# main.net
KiCad netlist of a schematic drawn in EAGLE
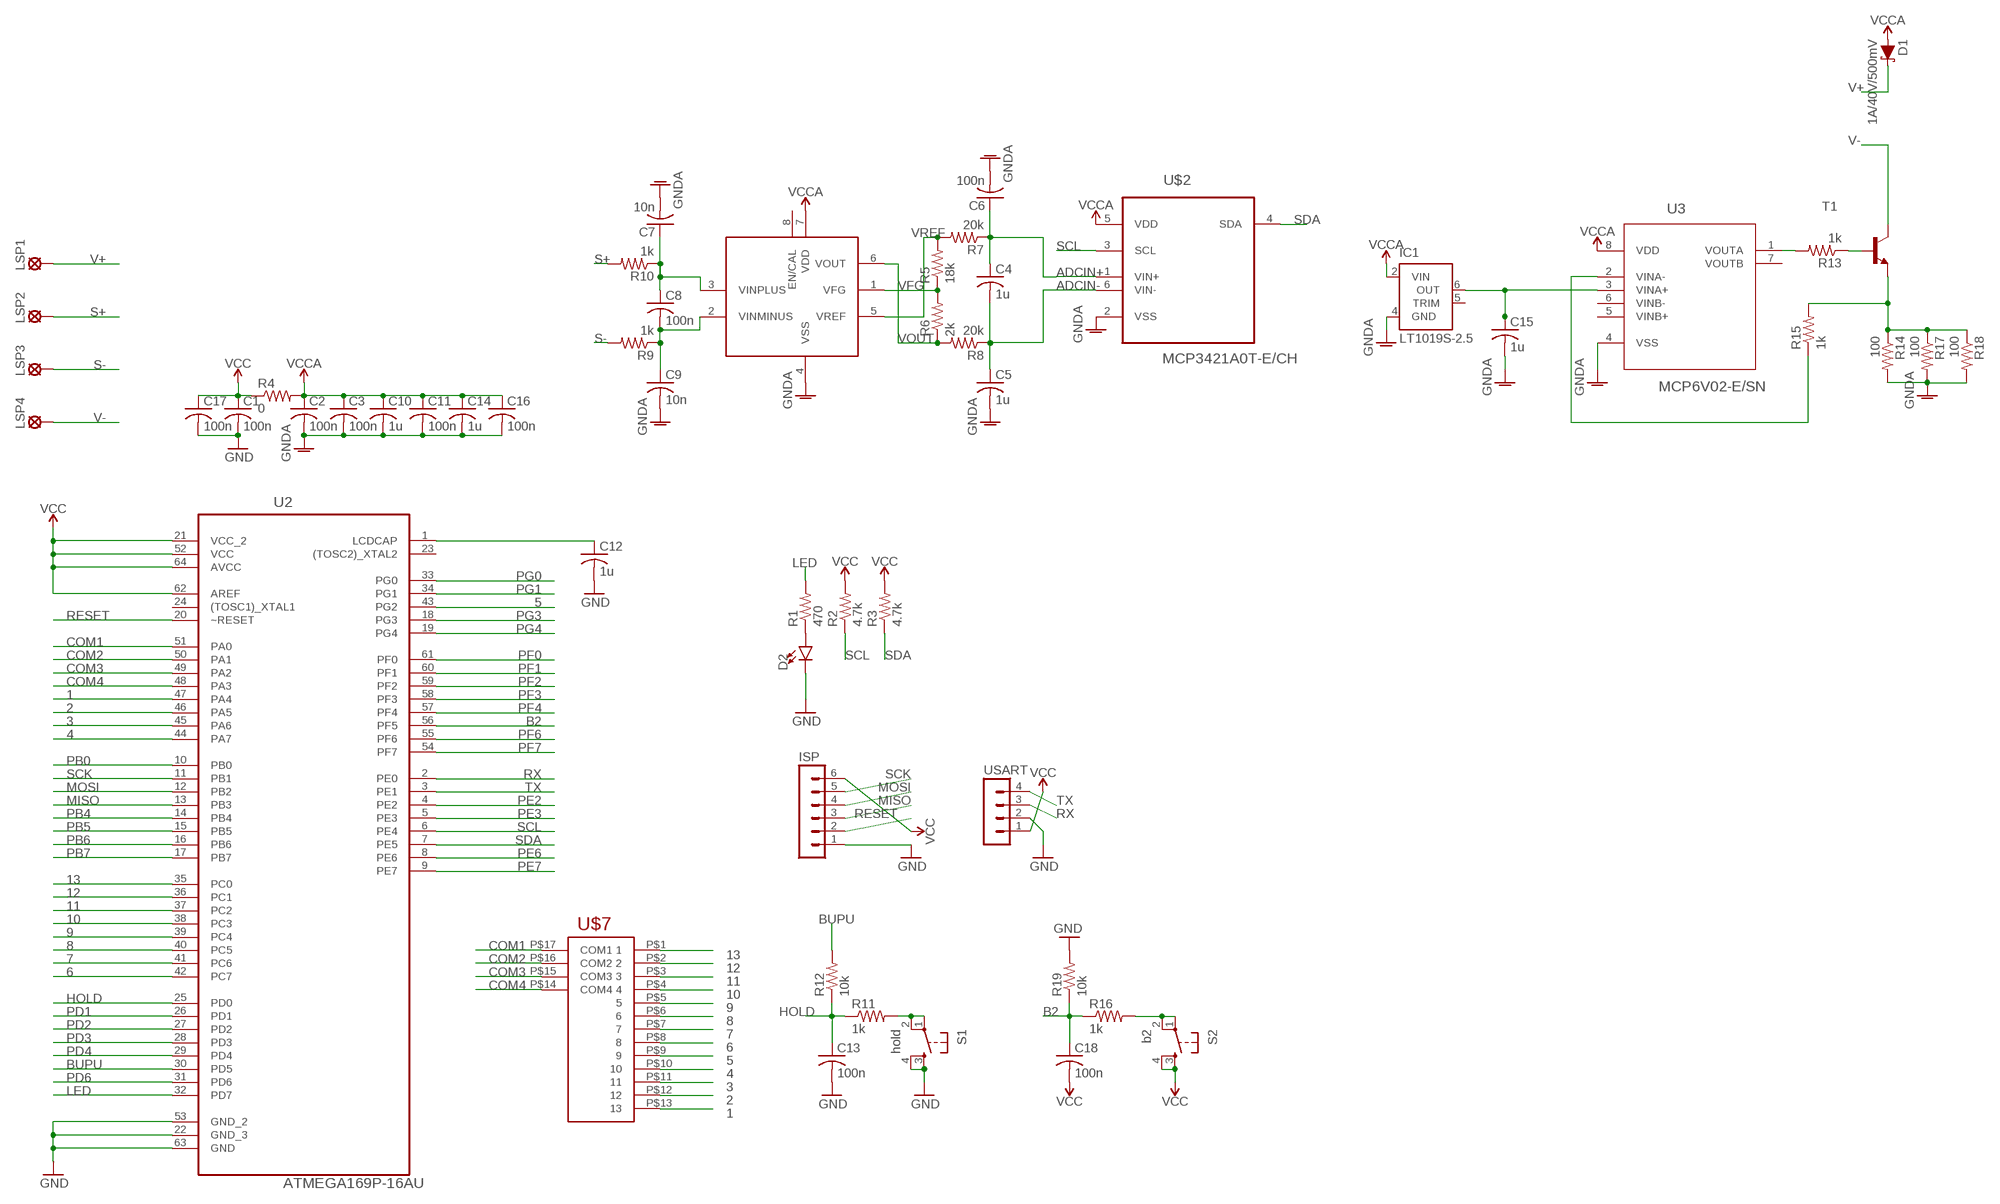
[diagram p0: schematic, sheet 1]

(export (version "E")
  (design (tool "Eeschema 10.0.6"))
  (components
    (comp (ref "C1")
      (value "100n")
      (footprint "eagle-import:C0603")
      (libsource (lib "eagle-import") (part "C-USC0603"))
    )
    (comp (ref "C2")
      (value "100n")
      (footprint "eagle-import:C0603")
      (libsource (lib "eagle-import") (part "C-USC0603"))
    )
    (comp (ref "C3")
      (value "100n")
      (footprint "eagle-import:C0603")
      (libsource (lib "eagle-import") (part "C-USC0603"))
    )
    (comp (ref "C4")
      (value "1u")
      (footprint "eagle-import:C0603")
      (libsource (lib "eagle-import") (part "C-USC0603"))
    )
    (comp (ref "C5")
      (value "1u")
      (footprint "eagle-import:C0603")
      (libsource (lib "eagle-import") (part "C-USC0603"))
    )
    (comp (ref "C6")
      (value "100n")
      (footprint "eagle-import:C0603")
      (libsource (lib "eagle-import") (part "C-USC0603"))
    )
    (comp (ref "C7")
      (value "10n")
      (footprint "eagle-import:C0603")
      (libsource (lib "eagle-import") (part "C-USC0603"))
    )
    (comp (ref "C8")
      (value "100n")
      (footprint "eagle-import:C0603")
      (libsource (lib "eagle-import") (part "C-USC0603"))
    )
    (comp (ref "C9")
      (value "10n")
      (footprint "eagle-import:C0603")
      (libsource (lib "eagle-import") (part "C-USC0603"))
    )
    (comp (ref "C10")
      (value "1u")
      (footprint "eagle-import:C0603")
      (libsource (lib "eagle-import") (part "C-USC0603"))
    )
    (comp (ref "C11")
      (value "100n")
      (footprint "eagle-import:C0603")
      (libsource (lib "eagle-import") (part "C-USC0603"))
    )
    (comp (ref "C12")
      (value "1u")
      (footprint "eagle-import:C0603")
      (libsource (lib "eagle-import") (part "C-USC0603"))
    )
    (comp (ref "C13")
      (value "100n")
      (footprint "eagle-import:C0603")
      (libsource (lib "eagle-import") (part "C-USC0603"))
    )
    (comp (ref "C14")
      (value "1u")
      (footprint "eagle-import:C0603")
      (libsource (lib "eagle-import") (part "C-USC0603"))
    )
    (comp (ref "C15")
      (value "1u")
      (footprint "eagle-import:C0603")
      (libsource (lib "eagle-import") (part "C-USC0603"))
    )
    (comp (ref "C16")
      (value "100n")
      (footprint "eagle-import:C0603")
      (libsource (lib "eagle-import") (part "C-USC0603"))
    )
    (comp (ref "C17")
      (value "100n")
      (footprint "eagle-import:C0603")
      (libsource (lib "eagle-import") (part "C-USC0603"))
    )
    (comp (ref "C18")
      (value "100n")
      (footprint "eagle-import:C0603")
      (libsource (lib "eagle-import") (part "C-USC0603"))
    )
    (comp (ref "D1")
      (value "1A/40V/500mV")
      (footprint "eagle-import:SMA-DIODE")
      (libsource (lib "eagle-import") (part "DIODE-SCHOTTKY-SS14"))
    )
    (comp (ref "D2")
      (value "LED5MM")
      (footprint "eagle-import:LED_5MM")
      (libsource (lib "eagle-import") (part "LED5MM"))
    )
    (comp (ref "IC1")
      (value "LT1019S-2.5")
      (footprint "eagle-import:SOIC8")
      (fields (field (name "MPN") "LT1019CS8-2.5#PBF"))
      (libsource (lib "eagle-import") (part "LT1019?S-2.5"))
    )
    (comp (ref "ISP")
      (value "MA06-1")
      (footprint "eagle-import:MA06-1")
      (libsource (lib "eagle-import") (part "MA06-1"))
    )
    (comp (ref "LSP1")
      (value "MCS08")
      (footprint "eagle-import:MCS08")
      (libsource (lib "eagle-import") (part "MCS08"))
    )
    (comp (ref "LSP2")
      (value "MCS08")
      (footprint "eagle-import:MCS08")
      (libsource (lib "eagle-import") (part "MCS08"))
    )
    (comp (ref "LSP3")
      (value "MCS08")
      (footprint "eagle-import:MCS08")
      (libsource (lib "eagle-import") (part "MCS08"))
    )
    (comp (ref "LSP4")
      (value "MCS08")
      (footprint "eagle-import:MCS08")
      (libsource (lib "eagle-import") (part "MCS08"))
    )
    (comp (ref "R1")
      (value "470")
      (footprint "eagle-import:R0603")
      (libsource (lib "eagle-import") (part "R-US_R0603"))
    )
    (comp (ref "R2")
      (value "4.7k")
      (footprint "eagle-import:R0603")
      (libsource (lib "eagle-import") (part "R-US_R0603"))
    )
    (comp (ref "R3")
      (value "4.7k")
      (footprint "eagle-import:R0603")
      (libsource (lib "eagle-import") (part "R-US_R0603"))
    )
    (comp (ref "R4")
      (value "0")
      (footprint "eagle-import:0309_12")
      (libsource (lib "eagle-import") (part "R-US_0309/12"))
    )
    (comp (ref "R5")
      (value "18k")
      (footprint "eagle-import:R0603")
      (libsource (lib "eagle-import") (part "R-US_R0603"))
    )
    (comp (ref "R6")
      (value "2k")
      (footprint "eagle-import:R0603")
      (libsource (lib "eagle-import") (part "R-US_R0603"))
    )
    (comp (ref "R7")
      (value "20k")
      (footprint "eagle-import:R0603")
      (libsource (lib "eagle-import") (part "R-US_R0603"))
    )
    (comp (ref "R8")
      (value "20k")
      (footprint "eagle-import:R0603")
      (libsource (lib "eagle-import") (part "R-US_R0603"))
    )
    (comp (ref "R9")
      (value "1k")
      (footprint "eagle-import:R0603")
      (libsource (lib "eagle-import") (part "R-US_R0603"))
    )
    (comp (ref "R10")
      (value "1k")
      (footprint "eagle-import:R0603")
      (libsource (lib "eagle-import") (part "R-US_R0603"))
    )
    (comp (ref "R11")
      (value "1k")
      (footprint "eagle-import:R0603")
      (libsource (lib "eagle-import") (part "R-US_R0603"))
    )
    (comp (ref "R12")
      (value "10k")
      (footprint "eagle-import:R0603")
      (libsource (lib "eagle-import") (part "R-US_R0603"))
    )
    (comp (ref "R13")
      (value "1k")
      (footprint "eagle-import:R0603")
      (libsource (lib "eagle-import") (part "R-US_R0603"))
    )
    (comp (ref "R14")
      (value "100")
      (footprint "eagle-import:R0603")
      (libsource (lib "eagle-import") (part "R-US_R0603"))
    )
    (comp (ref "R15")
      (value "1k")
      (footprint "eagle-import:R0603")
      (libsource (lib "eagle-import") (part "R-US_R0603"))
    )
    (comp (ref "R16")
      (value "1k")
      (footprint "eagle-import:R0603")
      (libsource (lib "eagle-import") (part "R-US_R0603"))
    )
    (comp (ref "R17")
      (value "100")
      (footprint "eagle-import:R0603")
      (libsource (lib "eagle-import") (part "R-US_R0603"))
    )
    (comp (ref "R18")
      (value "100")
      (footprint "eagle-import:R0603")
      (libsource (lib "eagle-import") (part "R-US_R0603"))
    )
    (comp (ref "R19")
      (value "10k")
      (footprint "eagle-import:R0603")
      (libsource (lib "eagle-import") (part "R-US_R0603"))
    )
    (comp (ref "S1")
      (value "hold")
      (footprint "eagle-import:TACTILE-PTH")
      (libsource (lib "eagle-import") (part "TAC_SWITCHPTH"))
    )
    (comp (ref "S2")
      (value "b2")
      (footprint "eagle-import:TACTILE-PTH")
      (libsource (lib "eagle-import") (part "TAC_SWITCHPTH"))
    )
    (comp (ref "T1")
      (value "MMBT3904LT1-NPN-SOT23-BEC")
      (footprint "eagle-import:SOT23-BEC")
      (libsource (lib "eagle-import") (part "-NPN-SOT23-BECMMBT3904LT1"))
    )
    (comp (ref "U$2")
      (value "MCP3421A0T-E/CH")
      (footprint "eagle-import:SOT95P270X145-6N")
      (libsource (lib "eagle-import") (part "MCP3421A0T-E/CH"))
    )
    (comp (ref "U$3")
      (value "MCP6N11")
      (footprint "eagle-import:SOIC8")
      (libsource (lib "eagle-import") (part "MCP6N11"))
    )
    (comp (ref "U$7")
      (value "GDC0570_LCD")
      (footprint "eagle-import:GDC0570_LCD")
      (libsource (lib "eagle-import") (part "GDC0570_LCD"))
    )
    (comp (ref "U2")
      (value "ATMEGA169P-16AU")
      (footprint "eagle-import:QFP80P1600X1600X120-64N")
      (libsource (lib "eagle-import") (part "ATMEGA169P-16AU"))
    )
    (comp (ref "U3")
      (value "MCP6V02-E/SN")
      (footprint "eagle-import:SOIC127P600X175-8N")
      (libsource (lib "eagle-import") (part "MCP6V02-E/SN"))
    )
    (comp (ref "USART")
      (value "MA04-1")
      (footprint "eagle-import:MA04-1")
      (libsource (lib "eagle-import") (part "MA04-1"))
    )
  )
  (nets
    (net (code "1") (name "/1") (class "Default")
      (node (ref "U$7") (pin "P$13") (pinfunction "13_P$13") (pintype "bidirectional"))
      (node (ref "U2") (pin "47") (pinfunction "PA4_47") (pintype "bidirectional"))
    )
    (net (code "2") (name "/2") (class "Default")
      (node (ref "U$7") (pin "P$12") (pinfunction "12_P$12") (pintype "bidirectional"))
      (node (ref "U2") (pin "46") (pinfunction "PA5_46") (pintype "bidirectional"))
    )
    (net (code "3") (name "/3") (class "Default")
      (node (ref "U$7") (pin "P$11") (pinfunction "11_P$11") (pintype "bidirectional"))
      (node (ref "U2") (pin "45") (pinfunction "PA6_45") (pintype "bidirectional"))
    )
    (net (code "4") (name "/4") (class "Default")
      (node (ref "U$7") (pin "P$10") (pinfunction "10_P$10") (pintype "bidirectional"))
      (node (ref "U2") (pin "44") (pinfunction "PA7_44") (pintype "bidirectional"))
    )
    (net (code "5") (name "/5") (class "Default")
      (node (ref "U$7") (pin "P$9") (pinfunction "9_P$9") (pintype "bidirectional"))
      (node (ref "U2") (pin "43") (pinfunction "PG2_43") (pintype "bidirectional"))
    )
    (net (code "6") (name "/6") (class "Default")
      (node (ref "U$7") (pin "P$8") (pinfunction "8_P$8") (pintype "bidirectional"))
      (node (ref "U2") (pin "42") (pinfunction "PC7_42") (pintype "bidirectional"))
    )
    (net (code "7") (name "/7") (class "Default")
      (node (ref "U$7") (pin "P$7") (pinfunction "7_P$7") (pintype "bidirectional"))
      (node (ref "U2") (pin "41") (pinfunction "PC6_41") (pintype "bidirectional"))
    )
    (net (code "8") (name "/8") (class "Default")
      (node (ref "U$7") (pin "P$6") (pinfunction "6_P$6") (pintype "bidirectional"))
      (node (ref "U2") (pin "40") (pinfunction "PC5_40") (pintype "bidirectional"))
    )
    (net (code "9") (name "/9") (class "Default")
      (node (ref "U$7") (pin "P$5") (pinfunction "5_P$5") (pintype "bidirectional"))
      (node (ref "U2") (pin "39") (pinfunction "PC4_39") (pintype "bidirectional"))
    )
    (net (code "10") (name "/10") (class "Default")
      (node (ref "U$7") (pin "P$4") (pinfunction "4_P$4") (pintype "bidirectional"))
      (node (ref "U2") (pin "38") (pinfunction "PC3_38") (pintype "bidirectional"))
    )
    (net (code "11") (name "/11") (class "Default")
      (node (ref "U$7") (pin "P$3") (pinfunction "3_P$3") (pintype "bidirectional"))
      (node (ref "U2") (pin "37") (pinfunction "PC2_37") (pintype "bidirectional"))
    )
    (net (code "12") (name "/12") (class "Default")
      (node (ref "U$7") (pin "P$2") (pinfunction "2_P$2") (pintype "bidirectional"))
      (node (ref "U2") (pin "36") (pinfunction "PC1_36") (pintype "bidirectional"))
    )
    (net (code "13") (name "/13") (class "Default")
      (node (ref "U$7") (pin "P$1") (pinfunction "1_P$1") (pintype "bidirectional"))
      (node (ref "U2") (pin "35") (pinfunction "PC0_35") (pintype "bidirectional"))
    )
    (net (code "14") (name "/ADCIN+") (class "Default")
      (node (ref "C4") (pin "1") (pinfunction "1_1") (pintype "passive"))
      (node (ref "C6") (pin "1") (pinfunction "1_1") (pintype "passive"))
      (node (ref "R7") (pin "1") (pinfunction "1_1") (pintype "passive"))
      (node (ref "U$2") (pin "1") (pinfunction "VIN+_1") (pintype "input"))
    )
    (net (code "15") (name "/ADCIN-") (class "Default")
      (node (ref "C4") (pin "2") (pinfunction "2_2") (pintype "passive"))
      (node (ref "C5") (pin "1") (pinfunction "1_1") (pintype "passive"))
      (node (ref "R8") (pin "1") (pinfunction "1_1") (pintype "passive"))
      (node (ref "U$2") (pin "6") (pinfunction "VIN-_6") (pintype "input"))
    )
    (net (code "16") (name "/B2") (class "Default")
      (node (ref "C18") (pin "1") (pinfunction "1_1") (pintype "passive"))
      (node (ref "R16") (pin "1") (pinfunction "1_1") (pintype "passive"))
      (node (ref "R19") (pin "1") (pinfunction "1_1") (pintype "passive"))
      (node (ref "U2") (pin "56") (pinfunction "PF5_56") (pintype "bidirectional"))
    )
    (net (code "17") (name "/BUPU") (class "Default")
      (node (ref "R12") (pin "2") (pinfunction "2_2") (pintype "passive"))
      (node (ref "U2") (pin "30") (pinfunction "PD5_30") (pintype "bidirectional"))
    )
    (net (code "18") (name "/COM1") (class "Default")
      (node (ref "U$7") (pin "P$17") (pinfunction "COM1_P$17") (pintype "bidirectional"))
      (node (ref "U2") (pin "51") (pinfunction "PA0_51") (pintype "bidirectional"))
    )
    (net (code "19") (name "/COM2") (class "Default")
      (node (ref "U$7") (pin "P$16") (pinfunction "COM2_P$16") (pintype "bidirectional"))
      (node (ref "U2") (pin "50") (pinfunction "PA1_50") (pintype "bidirectional"))
    )
    (net (code "20") (name "/COM3") (class "Default")
      (node (ref "U$7") (pin "P$15") (pinfunction "COM3_P$15") (pintype "bidirectional"))
      (node (ref "U2") (pin "49") (pinfunction "PA2_49") (pintype "bidirectional"))
    )
    (net (code "21") (name "/COM4") (class "Default")
      (node (ref "U$7") (pin "P$14") (pinfunction "COM4_P$14") (pintype "bidirectional"))
      (node (ref "U2") (pin "48") (pinfunction "PA3_48") (pintype "bidirectional"))
    )
    (net (code "22") (name "/HOLD") (class "Default")
      (node (ref "C13") (pin "1") (pinfunction "1_1") (pintype "passive"))
      (node (ref "R11") (pin "1") (pinfunction "1_1") (pintype "passive"))
      (node (ref "R12") (pin "1") (pinfunction "1_1") (pintype "passive"))
      (node (ref "U2") (pin "25") (pinfunction "PD0_25") (pintype "bidirectional"))
    )
    (net (code "23") (name "/LED") (class "Default")
      (node (ref "R1") (pin "2") (pinfunction "2_2") (pintype "passive"))
      (node (ref "U2") (pin "32") (pinfunction "PD7_32") (pintype "bidirectional"))
    )
    (net (code "24") (name "/MISO") (class "Default")
      (node (ref "ISP") (pin "3") (pinfunction "3_3") (pintype "passive"))
      (node (ref "U2") (pin "13") (pinfunction "PB3_13") (pintype "bidirectional"))
    )
    (net (code "25") (name "/MOSI") (class "Default")
      (node (ref "ISP") (pin "4") (pinfunction "4_4") (pintype "passive"))
      (node (ref "U2") (pin "12") (pinfunction "PB2_12") (pintype "bidirectional"))
    )
    (net (code "26") (name "/PB0") (class "Default")
      (node (ref "U2") (pin "10") (pinfunction "PB0_10") (pintype "bidirectional"))
    )
    (net (code "27") (name "/PB4") (class "Default")
      (node (ref "U2") (pin "14") (pinfunction "PB4_14") (pintype "bidirectional"))
    )
    (net (code "28") (name "/PB5") (class "Default")
      (node (ref "U2") (pin "15") (pinfunction "PB5_15") (pintype "bidirectional"))
    )
    (net (code "29") (name "/PB6") (class "Default")
      (node (ref "U2") (pin "16") (pinfunction "PB6_16") (pintype "bidirectional"))
    )
    (net (code "30") (name "/PB7") (class "Default")
      (node (ref "U2") (pin "17") (pinfunction "PB7_17") (pintype "bidirectional"))
    )
    (net (code "31") (name "/PD1") (class "Default")
      (node (ref "U2") (pin "26") (pinfunction "PD1_26") (pintype "bidirectional"))
    )
    (net (code "32") (name "/PD2") (class "Default")
      (node (ref "U2") (pin "27") (pinfunction "PD2_27") (pintype "bidirectional"))
    )
    (net (code "33") (name "/PD3") (class "Default")
      (node (ref "U2") (pin "28") (pinfunction "PD3_28") (pintype "bidirectional"))
    )
    (net (code "34") (name "/PD4") (class "Default")
      (node (ref "U2") (pin "29") (pinfunction "PD4_29") (pintype "bidirectional"))
    )
    (net (code "35") (name "/PD6") (class "Default")
      (node (ref "U2") (pin "31") (pinfunction "PD6_31") (pintype "bidirectional"))
    )
    (net (code "36") (name "/PE2") (class "Default")
      (node (ref "U2") (pin "4") (pinfunction "PE2_4") (pintype "bidirectional"))
    )
    (net (code "37") (name "/PE3") (class "Default")
      (node (ref "U2") (pin "5") (pinfunction "PE3_5") (pintype "bidirectional"))
    )
    (net (code "38") (name "/PE6") (class "Default")
      (node (ref "U2") (pin "8") (pinfunction "PE6_8") (pintype "bidirectional"))
    )
    (net (code "39") (name "/PE7") (class "Default")
      (node (ref "U2") (pin "9") (pinfunction "PE7_9") (pintype "bidirectional"))
    )
    (net (code "40") (name "/PF0") (class "Default")
      (node (ref "U2") (pin "61") (pinfunction "PF0_61") (pintype "bidirectional"))
    )
    (net (code "41") (name "/PF1") (class "Default")
      (node (ref "U2") (pin "60") (pinfunction "PF1_60") (pintype "bidirectional"))
    )
    (net (code "42") (name "/PF2") (class "Default")
      (node (ref "U2") (pin "59") (pinfunction "PF2_59") (pintype "bidirectional"))
    )
    (net (code "43") (name "/PF3") (class "Default")
      (node (ref "U2") (pin "58") (pinfunction "PF3_58") (pintype "bidirectional"))
    )
    (net (code "44") (name "/PF4") (class "Default")
      (node (ref "U2") (pin "57") (pinfunction "PF4_57") (pintype "bidirectional"))
    )
    (net (code "45") (name "/PF6") (class "Default")
      (node (ref "U2") (pin "55") (pinfunction "PF6_55") (pintype "bidirectional"))
    )
    (net (code "46") (name "/PF7") (class "Default")
      (node (ref "U2") (pin "54") (pinfunction "PF7_54") (pintype "bidirectional"))
    )
    (net (code "47") (name "/PG0") (class "Default")
      (node (ref "U2") (pin "33") (pinfunction "PG0_33") (pintype "bidirectional"))
    )
    (net (code "48") (name "/PG1") (class "Default")
      (node (ref "U2") (pin "34") (pinfunction "PG1_34") (pintype "bidirectional"))
    )
    (net (code "49") (name "/PG3") (class "Default")
      (node (ref "U2") (pin "18") (pinfunction "PG3_18") (pintype "bidirectional"))
    )
    (net (code "50") (name "/PG4") (class "Default")
      (node (ref "U2") (pin "19") (pinfunction "PG4_19") (pintype "bidirectional"))
    )
    (net (code "51") (name "/RESET") (class "Default")
      (node (ref "ISP") (pin "2") (pinfunction "2_2") (pintype "passive"))
      (node (ref "U2") (pin "20") (pinfunction "~{RESET}_20") (pintype "input"))
    )
    (net (code "52") (name "/RX") (class "Default")
      (node (ref "U2") (pin "2") (pinfunction "PE0_2") (pintype "bidirectional"))
      (node (ref "USART") (pin "3") (pinfunction "3_3") (pintype "passive"))
    )
    (net (code "53") (name "/S+") (class "Default")
      (node (ref "LSP2") (pin "MP") (pinfunction "MP_MP") (pintype "passive"))
      (node (ref "R10") (pin "2") (pinfunction "2_2") (pintype "passive"))
    )
    (net (code "54") (name "/S-") (class "Default")
      (node (ref "LSP3") (pin "MP") (pinfunction "MP_MP") (pintype "passive"))
      (node (ref "R9") (pin "2") (pinfunction "2_2") (pintype "passive"))
    )
    (net (code "55") (name "/SCK") (class "Default")
      (node (ref "ISP") (pin "5") (pinfunction "5_5") (pintype "passive"))
      (node (ref "U2") (pin "11") (pinfunction "PB1_11") (pintype "bidirectional"))
    )
    (net (code "56") (name "/SCL") (class "Default")
      (node (ref "R2") (pin "1") (pinfunction "1_1") (pintype "passive"))
      (node (ref "U$2") (pin "3") (pinfunction "SCL_3") (pintype "input"))
      (node (ref "U2") (pin "6") (pinfunction "PE4_6") (pintype "bidirectional"))
    )
    (net (code "57") (name "/SDA") (class "Default")
      (node (ref "R3") (pin "1") (pinfunction "1_1") (pintype "passive"))
      (node (ref "U$2") (pin "4") (pinfunction "SDA_4") (pintype "bidirectional"))
      (node (ref "U2") (pin "7") (pinfunction "PE5_7") (pintype "bidirectional"))
    )
    (net (code "58") (name "/TX") (class "Default")
      (node (ref "U2") (pin "3") (pinfunction "PE1_3") (pintype "bidirectional"))
      (node (ref "USART") (pin "4") (pinfunction "4_4") (pintype "passive"))
    )
    (net (code "59") (name "/V+") (class "Default")
      (node (ref "D1") (pin "C") (pinfunction "C_C") (pintype "passive"))
      (node (ref "LSP1") (pin "MP") (pinfunction "MP_MP") (pintype "passive"))
    )
    (net (code "60") (name "/V-") (class "Default")
      (node (ref "LSP4") (pin "MP") (pinfunction "MP_MP") (pintype "passive"))
      (node (ref "T1") (pin "C") (pinfunction "C_C") (pintype "passive"))
    )
    (net (code "61") (name "/VFG") (class "Default")
      (node (ref "R5") (pin "1") (pinfunction "1_1") (pintype "passive"))
      (node (ref "R6") (pin "2") (pinfunction "2_2") (pintype "passive"))
      (node (ref "U$3") (pin "1") (pinfunction "VFG_1") (pintype "bidirectional"))
    )
    (net (code "62") (name "/VOUT") (class "Default")
      (node (ref "R6") (pin "1") (pinfunction "1_1") (pintype "passive"))
      (node (ref "R8") (pin "2") (pinfunction "2_2") (pintype "passive"))
      (node (ref "U$3") (pin "6") (pinfunction "VOUT_6") (pintype "bidirectional"))
    )
    (net (code "63") (name "/VREF") (class "Default")
      (node (ref "R5") (pin "2") (pinfunction "2_2") (pintype "passive"))
      (node (ref "R7") (pin "2") (pinfunction "2_2") (pintype "passive"))
      (node (ref "U$3") (pin "5") (pinfunction "VREF_5") (pintype "bidirectional"))
    )
    (net (code "64") (name "GND") (class "Default")
      (node (ref "C1") (pin "2") (pinfunction "2_2") (pintype "passive"))
      (node (ref "C12") (pin "2") (pinfunction "2_2") (pintype "passive"))
      (node (ref "C13") (pin "2") (pinfunction "2_2") (pintype "passive"))
      (node (ref "C17") (pin "2") (pinfunction "2_2") (pintype "passive"))
      (node (ref "D2") (pin "K") (pinfunction "C_K") (pintype "passive"))
      (node (ref "ISP") (pin "1") (pinfunction "1_1") (pintype "passive"))
      (node (ref "R19") (pin "2") (pinfunction "2_2") (pintype "passive"))
      (node (ref "S1") (pin "3") (pinfunction "3_3") (pintype "passive"))
      (node (ref "S1") (pin "4") (pinfunction "4_4") (pintype "passive"))
      (node (ref "U2") (pin "22") (pinfunction "GND_3_22") (pintype "passive"))
      (node (ref "U2") (pin "53") (pinfunction "GND_2_53") (pintype "passive"))
      (node (ref "U2") (pin "63") (pinfunction "GND_63") (pintype "passive"))
      (node (ref "USART") (pin "2") (pinfunction "2_2") (pintype "passive"))
    )
    (net (code "65") (name "GNDA") (class "Default")
      (node (ref "C10") (pin "2") (pinfunction "2_2") (pintype "passive"))
      (node (ref "C11") (pin "2") (pinfunction "2_2") (pintype "passive"))
      (node (ref "C14") (pin "2") (pinfunction "2_2") (pintype "passive"))
      (node (ref "C15") (pin "2") (pinfunction "2_2") (pintype "passive"))
      (node (ref "C16") (pin "2") (pinfunction "2_2") (pintype "passive"))
      (node (ref "C2") (pin "2") (pinfunction "2_2") (pintype "passive"))
      (node (ref "C3") (pin "2") (pinfunction "2_2") (pintype "passive"))
      (node (ref "C5") (pin "2") (pinfunction "2_2") (pintype "passive"))
      (node (ref "C6") (pin "2") (pinfunction "2_2") (pintype "passive"))
      (node (ref "C7") (pin "2") (pinfunction "2_2") (pintype "passive"))
      (node (ref "C9") (pin "2") (pinfunction "2_2") (pintype "passive"))
      (node (ref "IC1") (pin "4") (pinfunction "GND_4") (pintype "power_in"))
      (node (ref "R14") (pin "2") (pinfunction "2_2") (pintype "passive"))
      (node (ref "R17") (pin "2") (pinfunction "2_2") (pintype "passive"))
      (node (ref "R18") (pin "2") (pinfunction "2_2") (pintype "passive"))
      (node (ref "U$2") (pin "2") (pinfunction "VSS_2") (pintype "passive"))
      (node (ref "U$3") (pin "4") (pinfunction "VSS_4") (pintype "bidirectional"))
      (node (ref "U3") (pin "4") (pinfunction "VSS_4") (pintype "power_in"))
    )
    (net (code "66") (name "Net-(D2-PadA)") (class "Default")
      (node (ref "D2") (pin "A") (pinfunction "A_A") (pintype "passive"))
      (node (ref "R1") (pin "1") (pinfunction "1_1") (pintype "passive"))
    )
    (net (code "67") (name "Net-(IC1-OUT)") (class "Default")
      (node (ref "C15") (pin "1") (pinfunction "1_1") (pintype "passive"))
      (node (ref "IC1") (pin "6") (pinfunction "OUT_6") (pintype "input"))
      (node (ref "U3") (pin "3") (pinfunction "VINA+_3") (pintype "input"))
    )
    (net (code "68") (name "Net-(R11-Pad2)") (class "Default")
      (node (ref "R11") (pin "2") (pinfunction "2_2") (pintype "passive"))
      (node (ref "S1") (pin "1") (pinfunction "1_1") (pintype "passive"))
      (node (ref "S1") (pin "2") (pinfunction "2_2") (pintype "passive"))
    )
    (net (code "69") (name "Net-(R13-Pad1)") (class "Default")
      (node (ref "R13") (pin "1") (pinfunction "1_1") (pintype "passive"))
      (node (ref "T1") (pin "B") (pinfunction "B_B") (pintype "passive"))
    )
    (net (code "70") (name "Net-(R14-Pad1)") (class "Default")
      (node (ref "R14") (pin "1") (pinfunction "1_1") (pintype "passive"))
      (node (ref "R15") (pin "2") (pinfunction "2_2") (pintype "passive"))
      (node (ref "R17") (pin "1") (pinfunction "1_1") (pintype "passive"))
      (node (ref "R18") (pin "1") (pinfunction "1_1") (pintype "passive"))
      (node (ref "T1") (pin "E") (pinfunction "E_E") (pintype "passive"))
    )
    (net (code "71") (name "Net-(R16-Pad2)") (class "Default")
      (node (ref "R16") (pin "2") (pinfunction "2_2") (pintype "passive"))
      (node (ref "S2") (pin "1") (pinfunction "1_1") (pintype "passive"))
      (node (ref "S2") (pin "2") (pinfunction "2_2") (pintype "passive"))
    )
    (net (code "72") (name "Net-(U$3-VINMINUS)") (class "Default")
      (node (ref "C8") (pin "2") (pinfunction "2_2") (pintype "passive"))
      (node (ref "C9") (pin "1") (pinfunction "1_1") (pintype "passive"))
      (node (ref "R9") (pin "1") (pinfunction "1_1") (pintype "passive"))
      (node (ref "U$3") (pin "2") (pinfunction "VINMINUS_2") (pintype "bidirectional"))
    )
    (net (code "73") (name "Net-(U$3-VINPLUS)") (class "Default")
      (node (ref "C7") (pin "1") (pinfunction "1_1") (pintype "passive"))
      (node (ref "C8") (pin "1") (pinfunction "1_1") (pintype "passive"))
      (node (ref "R10") (pin "1") (pinfunction "1_1") (pintype "passive"))
      (node (ref "U$3") (pin "3") (pinfunction "VINPLUS_3") (pintype "bidirectional"))
    )
    (net (code "74") (name "Net-(U2-LCDCAP)") (class "Default")
      (node (ref "C12") (pin "1") (pinfunction "1_1") (pintype "passive"))
      (node (ref "U2") (pin "1") (pinfunction "LCDCAP_1") (pintype "passive"))
    )
    (net (code "75") (name "Net-(U3-VINA-)") (class "Default")
      (node (ref "R15") (pin "1") (pinfunction "1_1") (pintype "passive"))
      (node (ref "U3") (pin "2") (pinfunction "VINA-_2") (pintype "input"))
    )
    (net (code "76") (name "Net-(U3-VOUTA)") (class "Default")
      (node (ref "R13") (pin "2") (pinfunction "2_2") (pintype "passive"))
      (node (ref "U3") (pin "1") (pinfunction "VOUTA_1") (pintype "output"))
    )
    (net (code "77") (name "VCC") (class "Default")
      (node (ref "C1") (pin "1") (pinfunction "1_1") (pintype "passive"))
      (node (ref "C17") (pin "1") (pinfunction "1_1") (pintype "passive"))
      (node (ref "C18") (pin "2") (pinfunction "2_2") (pintype "passive"))
      (node (ref "ISP") (pin "6") (pinfunction "6_6") (pintype "passive"))
      (node (ref "R2") (pin "2") (pinfunction "2_2") (pintype "passive"))
      (node (ref "R3") (pin "2") (pinfunction "2_2") (pintype "passive"))
      (node (ref "R4") (pin "1") (pinfunction "1_1") (pintype "passive"))
      (node (ref "S2") (pin "3") (pinfunction "3_3") (pintype "passive"))
      (node (ref "S2") (pin "4") (pinfunction "4_4") (pintype "passive"))
      (node (ref "U2") (pin "21") (pinfunction "VCC_2_21") (pintype "power_in"))
      (node (ref "U2") (pin "52") (pinfunction "VCC_52") (pintype "power_in"))
      (node (ref "U2") (pin "62") (pinfunction "AREF_62") (pintype "input"))
      (node (ref "U2") (pin "64") (pinfunction "AVCC_64") (pintype "power_in"))
      (node (ref "USART") (pin "1") (pinfunction "1_1") (pintype "passive"))
    )
    (net (code "78") (name "VCCA") (class "Default")
      (node (ref "C10") (pin "1") (pinfunction "1_1") (pintype "passive"))
      (node (ref "C11") (pin "1") (pinfunction "1_1") (pintype "passive"))
      (node (ref "C14") (pin "1") (pinfunction "1_1") (pintype "passive"))
      (node (ref "C16") (pin "1") (pinfunction "1_1") (pintype "passive"))
      (node (ref "C2") (pin "1") (pinfunction "1_1") (pintype "passive"))
      (node (ref "C3") (pin "1") (pinfunction "1_1") (pintype "passive"))
      (node (ref "D1") (pin "A") (pinfunction "A_A") (pintype "passive"))
      (node (ref "IC1") (pin "2") (pinfunction "VIN_2") (pintype "input"))
      (node (ref "R4") (pin "2") (pinfunction "2_2") (pintype "passive"))
      (node (ref "U$2") (pin "5") (pinfunction "VDD_5") (pintype "power_in"))
      (node (ref "U$3") (pin "7") (pinfunction "VDD_7") (pintype "bidirectional"))
      (node (ref "U3") (pin "8") (pinfunction "VDD_8") (pintype "power_in"))
    )
    (net (code "79") (name "unconnected-(IC1-TRIM-Pad5)") (class "Default")
      (node (ref "IC1") (pin "5") (pinfunction "TRIM_5") (pintype "passive"))
    )
    (net (code "80") (name "unconnected-(U$3-EN{slash}CAL-Pad8)") (class "Default")
      (node (ref "U$3") (pin "8") (pinfunction "EN/CAL_8") (pintype "bidirectional"))
    )
    (net (code "81") (name "unconnected-(U2-(TOSC1)_XTAL1-Pad24)") (class "Default")
      (node (ref "U2") (pin "24") (pinfunction "(TOSC1)_XTAL1_24") (pintype "input"))
    )
    (net (code "82") (name "unconnected-(U2-(TOSC2)_XTAL2-Pad23)") (class "Default")
      (node (ref "U2") (pin "23") (pinfunction "(TOSC2)_XTAL2_23") (pintype "output"))
    )
    (net (code "83") (name "unconnected-(U3-VINB+-Pad5)") (class "Default")
      (node (ref "U3") (pin "5") (pinfunction "VINB+_5") (pintype "input"))
    )
    (net (code "84") (name "unconnected-(U3-VINB--Pad6)") (class "Default")
      (node (ref "U3") (pin "6") (pinfunction "VINB-_6") (pintype "input"))
    )
    (net (code "85") (name "unconnected-(U3-VOUTB-Pad7)") (class "Default")
      (node (ref "U3") (pin "7") (pinfunction "VOUTB_7") (pintype "output"))
    )
  )
)
